# PushButton_RGB1.net
KiCad netlist of a schematic drawn in EAGLE
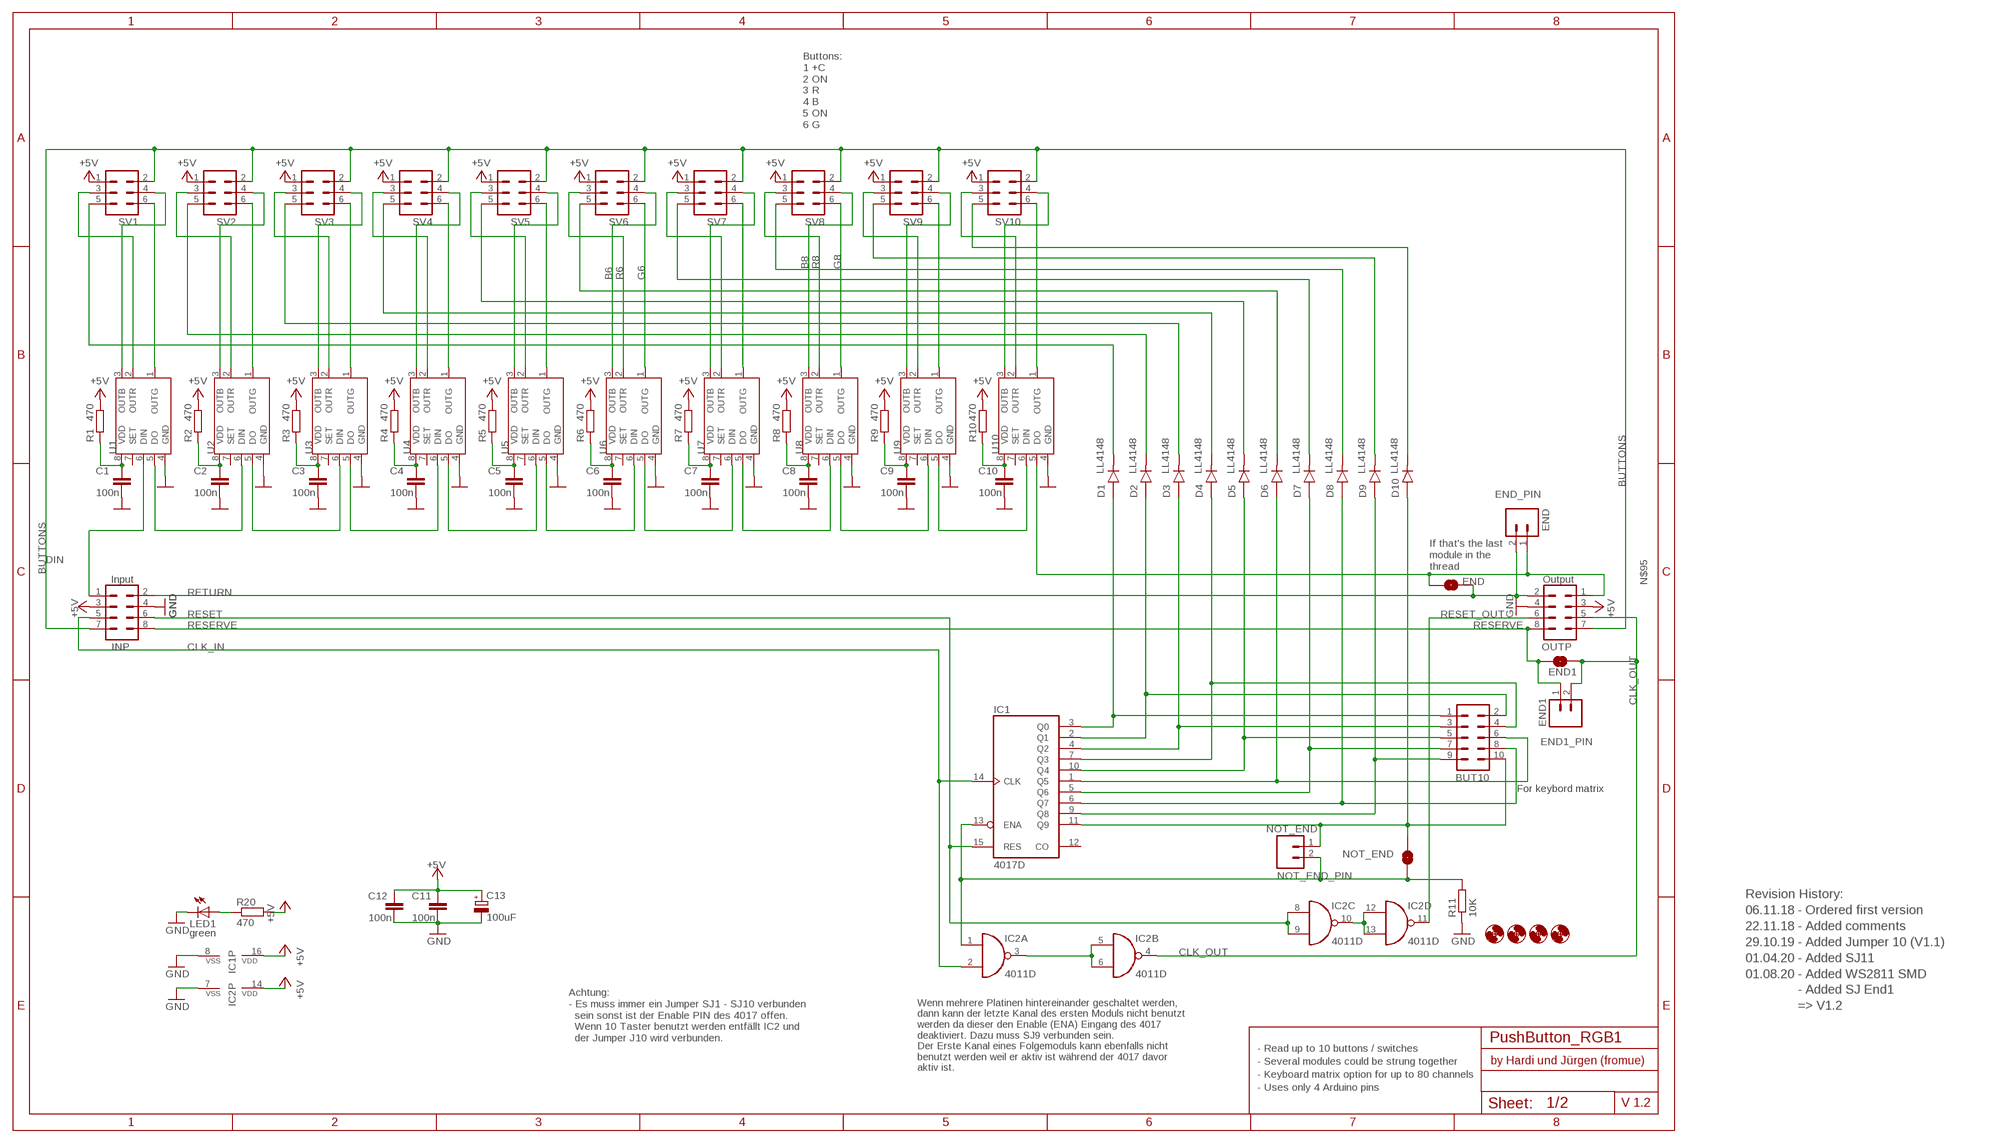
[diagram p0: schematic, sheet 1]
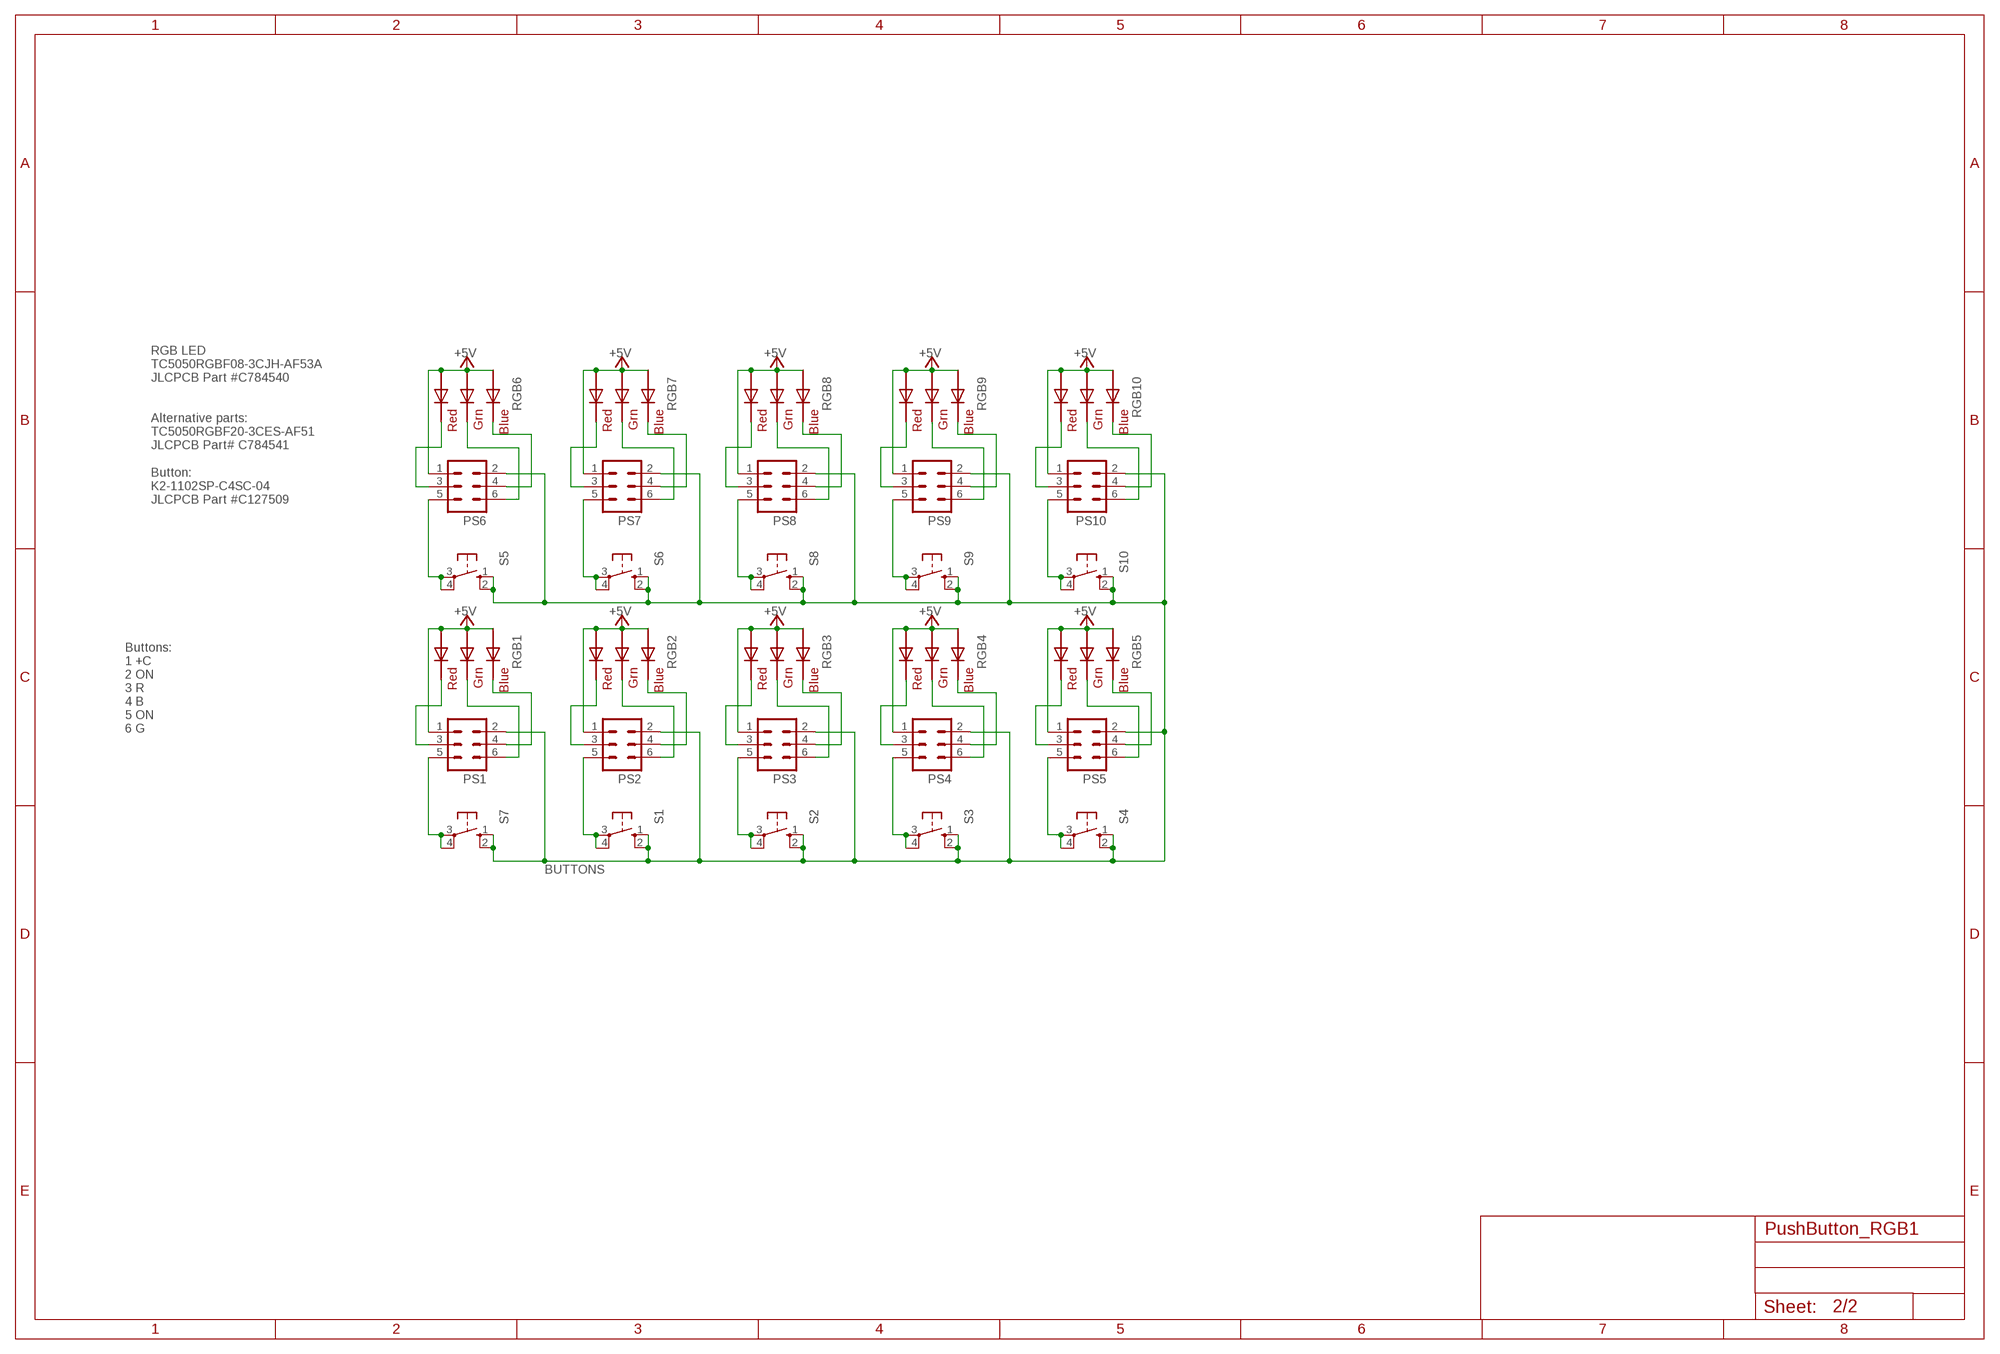
[diagram p1: schematic, sheet 2]

(export (version "E")
  (design (tool "Eeschema 10.0.6"))
  (components
    (comp (ref "PS1")
      (value "CON-HARTING-ML_ML6BKL10120958")
      (footprint "eagle-import:BKL10120958_MIRROR")
      (libsource (lib "eagle-import") (part "CON-HARTING-ML_ML6BKL10120958"))
    )
    (comp (ref "PS2")
      (value "CON-HARTING-ML_ML6BKL10120958")
      (footprint "eagle-import:BKL10120958_MIRROR")
      (libsource (lib "eagle-import") (part "CON-HARTING-ML_ML6BKL10120958"))
    )
    (comp (ref "PS3")
      (value "CON-HARTING-ML_ML6BKL10120958")
      (footprint "eagle-import:BKL10120958_MIRROR")
      (libsource (lib "eagle-import") (part "CON-HARTING-ML_ML6BKL10120958"))
    )
    (comp (ref "PS4")
      (value "CON-HARTING-ML_ML6BKL10120958")
      (footprint "eagle-import:BKL10120958_MIRROR")
      (libsource (lib "eagle-import") (part "CON-HARTING-ML_ML6BKL10120958"))
    )
    (comp (ref "PS5")
      (value "CON-HARTING-ML_ML6BKL10120958")
      (footprint "eagle-import:BKL10120958_MIRROR")
      (libsource (lib "eagle-import") (part "CON-HARTING-ML_ML6BKL10120958"))
    )
    (comp (ref "PS6")
      (value "CON-HARTING-ML_ML6BKL10120958")
      (footprint "eagle-import:BKL10120958_MIRROR")
      (libsource (lib "eagle-import") (part "CON-HARTING-ML_ML6BKL10120958"))
    )
    (comp (ref "PS7")
      (value "CON-HARTING-ML_ML6BKL10120958")
      (footprint "eagle-import:BKL10120958_MIRROR")
      (libsource (lib "eagle-import") (part "CON-HARTING-ML_ML6BKL10120958"))
    )
    (comp (ref "PS8")
      (value "CON-HARTING-ML_ML6BKL10120958")
      (footprint "eagle-import:BKL10120958_MIRROR")
      (libsource (lib "eagle-import") (part "CON-HARTING-ML_ML6BKL10120958"))
    )
    (comp (ref "PS9")
      (value "CON-HARTING-ML_ML6BKL10120958")
      (footprint "eagle-import:BKL10120958_MIRROR")
      (libsource (lib "eagle-import") (part "CON-HARTING-ML_ML6BKL10120958"))
    )
    (comp (ref "PS10")
      (value "CON-HARTING-ML_ML6BKL10120958")
      (footprint "eagle-import:BKL10120958_MIRROR")
      (libsource (lib "eagle-import") (part "CON-HARTING-ML_ML6BKL10120958"))
    )
    (comp (ref "RGB1")
      (value "RGBLED5050")
      (footprint "eagle-import:RGBLED5050")
      (libsource (lib "eagle-import") (part "RGBLED5050"))
    )
    (comp (ref "RGB2")
      (value "RGBLED5050")
      (footprint "eagle-import:RGBLED5050")
      (libsource (lib "eagle-import") (part "RGBLED5050"))
    )
    (comp (ref "RGB3")
      (value "RGBLED5050")
      (footprint "eagle-import:RGBLED5050")
      (libsource (lib "eagle-import") (part "RGBLED5050"))
    )
    (comp (ref "RGB4")
      (value "RGBLED5050")
      (footprint "eagle-import:RGBLED5050")
      (libsource (lib "eagle-import") (part "RGBLED5050"))
    )
    (comp (ref "RGB5")
      (value "RGBLED5050")
      (footprint "eagle-import:RGBLED5050")
      (libsource (lib "eagle-import") (part "RGBLED5050"))
    )
    (comp (ref "RGB6")
      (value "RGBLED5050")
      (footprint "eagle-import:RGBLED5050")
      (libsource (lib "eagle-import") (part "RGBLED5050"))
    )
    (comp (ref "RGB7")
      (value "RGBLED5050")
      (footprint "eagle-import:RGBLED5050")
      (libsource (lib "eagle-import") (part "RGBLED5050"))
    )
    (comp (ref "RGB8")
      (value "RGBLED5050")
      (footprint "eagle-import:RGBLED5050")
      (libsource (lib "eagle-import") (part "RGBLED5050"))
    )
    (comp (ref "RGB9")
      (value "RGBLED5050")
      (footprint "eagle-import:RGBLED5050")
      (libsource (lib "eagle-import") (part "RGBLED5050"))
    )
    (comp (ref "RGB10")
      (value "RGBLED5050")
      (footprint "eagle-import:RGBLED5050")
      (libsource (lib "eagle-import") (part "RGBLED5050"))
    )
    (comp (ref "S1")
      (value "10-XXB3F-10XX_SMD")
      (footprint "eagle-import:B3F-10XX_SMD")
      (libsource (lib "eagle-import") (part "10-XXB3F-10XX_SMD"))
    )
    (comp (ref "S2")
      (value "10-XXB3F-10XX_SMD")
      (footprint "eagle-import:B3F-10XX_SMD")
      (libsource (lib "eagle-import") (part "10-XXB3F-10XX_SMD"))
    )
    (comp (ref "S3")
      (value "10-XXB3F-10XX_SMD")
      (footprint "eagle-import:B3F-10XX_SMD")
      (libsource (lib "eagle-import") (part "10-XXB3F-10XX_SMD"))
    )
    (comp (ref "S4")
      (value "10-XXB3F-10XX_SMD")
      (footprint "eagle-import:B3F-10XX_SMD")
      (libsource (lib "eagle-import") (part "10-XXB3F-10XX_SMD"))
    )
    (comp (ref "S5")
      (value "10-XXB3F-10XX_SMD")
      (footprint "eagle-import:B3F-10XX_SMD")
      (libsource (lib "eagle-import") (part "10-XXB3F-10XX_SMD"))
    )
    (comp (ref "S6")
      (value "10-XXB3F-10XX_SMD")
      (footprint "eagle-import:B3F-10XX_SMD")
      (libsource (lib "eagle-import") (part "10-XXB3F-10XX_SMD"))
    )
    (comp (ref "S7")
      (value "10-XXB3F-10XX_SMD")
      (footprint "eagle-import:B3F-10XX_SMD")
      (libsource (lib "eagle-import") (part "10-XXB3F-10XX_SMD"))
    )
    (comp (ref "S8")
      (value "10-XXB3F-10XX_SMD")
      (footprint "eagle-import:B3F-10XX_SMD")
      (libsource (lib "eagle-import") (part "10-XXB3F-10XX_SMD"))
    )
    (comp (ref "S9")
      (value "10-XXB3F-10XX_SMD")
      (footprint "eagle-import:B3F-10XX_SMD")
      (libsource (lib "eagle-import") (part "10-XXB3F-10XX_SMD"))
    )
    (comp (ref "S10")
      (value "10-XXB3F-10XX_SMD")
      (footprint "eagle-import:B3F-10XX_SMD")
      (libsource (lib "eagle-import") (part "10-XXB3F-10XX_SMD"))
    )
    (comp (ref "BUT10")
      (value "CON-HARTING-ML_ML10")
      (footprint "eagle-import:CON-HARTING-ML_ML10")
      (libsource (lib "eagle-import") (part "CON-HARTING-ML_ML10"))
    )
    (comp (ref "C1")
      (value "100n")
      (footprint "eagle-import:C0603")
      (libsource (lib "eagle-import") (part "C-EUC0603"))
    )
    (comp (ref "C2")
      (value "100n")
      (footprint "eagle-import:C0603")
      (libsource (lib "eagle-import") (part "C-EUC0603"))
    )
    (comp (ref "C3")
      (value "100n")
      (footprint "eagle-import:C0603")
      (libsource (lib "eagle-import") (part "C-EUC0603"))
    )
    (comp (ref "C4")
      (value "100n")
      (footprint "eagle-import:C0603")
      (libsource (lib "eagle-import") (part "C-EUC0603"))
    )
    (comp (ref "C5")
      (value "100n")
      (footprint "eagle-import:C0603")
      (libsource (lib "eagle-import") (part "C-EUC0603"))
    )
    (comp (ref "C6")
      (value "100n")
      (footprint "eagle-import:C0603")
      (libsource (lib "eagle-import") (part "C-EUC0603"))
    )
    (comp (ref "C7")
      (value "100n")
      (footprint "eagle-import:C0603")
      (libsource (lib "eagle-import") (part "C-EUC0603"))
    )
    (comp (ref "C8")
      (value "100n")
      (footprint "eagle-import:C0603")
      (libsource (lib "eagle-import") (part "C-EUC0603"))
    )
    (comp (ref "C9")
      (value "100n")
      (footprint "eagle-import:C0603")
      (libsource (lib "eagle-import") (part "C-EUC0603"))
    )
    (comp (ref "C10")
      (value "100n")
      (footprint "eagle-import:C0603")
      (libsource (lib "eagle-import") (part "C-EUC0603"))
    )
    (comp (ref "C11")
      (value "100n")
      (footprint "eagle-import:C0603")
      (libsource (lib "eagle-import") (part "C-EUC0603"))
    )
    (comp (ref "C12")
      (value "100n")
      (footprint "eagle-import:C0603")
      (libsource (lib "eagle-import") (part "C-EUC0603"))
    )
    (comp (ref "C13")
      (value "100uF")
      (footprint "eagle-import:D_7343-31W")
      (libsource (lib "eagle-import") (part "CPOL-EUD/7343-31W"))
    )
    (comp (ref "D1")
      (value "LL4148")
      (footprint "eagle-import:DIO_LL4148")
      (fields (field (name "MF") "ON"))
      (libsource (lib "eagle-import") (part "LL4148"))
    )
    (comp (ref "D2")
      (value "LL4148")
      (footprint "eagle-import:DIO_LL4148")
      (fields (field (name "MF") "ON"))
      (libsource (lib "eagle-import") (part "LL4148"))
    )
    (comp (ref "D3")
      (value "LL4148")
      (footprint "eagle-import:DIO_LL4148")
      (fields (field (name "MF") "ON"))
      (libsource (lib "eagle-import") (part "LL4148"))
    )
    (comp (ref "D4")
      (value "LL4148")
      (footprint "eagle-import:DIO_LL4148")
      (fields (field (name "MF") "ON"))
      (libsource (lib "eagle-import") (part "LL4148"))
    )
    (comp (ref "D5")
      (value "LL4148")
      (footprint "eagle-import:DIO_LL4148")
      (fields (field (name "MF") "ON"))
      (libsource (lib "eagle-import") (part "LL4148"))
    )
    (comp (ref "D6")
      (value "LL4148")
      (footprint "eagle-import:DIO_LL4148")
      (fields (field (name "MF") "ON"))
      (libsource (lib "eagle-import") (part "LL4148"))
    )
    (comp (ref "D7")
      (value "LL4148")
      (footprint "eagle-import:DIO_LL4148")
      (fields (field (name "MF") "ON"))
      (libsource (lib "eagle-import") (part "LL4148"))
    )
    (comp (ref "D8")
      (value "LL4148")
      (footprint "eagle-import:DIO_LL4148")
      (fields (field (name "MF") "ON"))
      (libsource (lib "eagle-import") (part "LL4148"))
    )
    (comp (ref "D9")
      (value "LL4148")
      (footprint "eagle-import:DIO_LL4148")
      (fields (field (name "MF") "ON"))
      (libsource (lib "eagle-import") (part "LL4148"))
    )
    (comp (ref "D10")
      (value "LL4148")
      (footprint "eagle-import:DIO_LL4148")
      (fields (field (name "MF") "ON"))
      (libsource (lib "eagle-import") (part "LL4148"))
    )
    (comp (ref "END")
      (value "SOLDERJUMPERNO")
      (footprint "eagle-import:SJ_2S-NO")
      (libsource (lib "eagle-import") (part "SOLDERJUMPERNO"))
    )
    (comp (ref "END1")
      (value "SOLDERJUMPERNO")
      (footprint "eagle-import:SJ_2S-NO")
      (libsource (lib "eagle-import") (part "SOLDERJUMPERNO"))
    )
    (comp (ref "END1_PIN")
      (value "END1")
      (footprint "eagle-import:1X02")
      (libsource (lib "eagle-import") (part "M02PTH"))
    )
    (comp (ref "END_PIN")
      (value "END")
      (footprint "eagle-import:1X02")
      (libsource (lib "eagle-import") (part "M02PTH"))
    )
    (comp (ref "H1")
      (value "MOUNT-HOLE3.0")
      (footprint "eagle-import:3,0")
      (libsource (lib "eagle-import") (part "MOUNT-HOLE3.0"))
    )
    (comp (ref "H2")
      (value "MOUNT-HOLE3.0")
      (footprint "eagle-import:3,0")
      (libsource (lib "eagle-import") (part "MOUNT-HOLE3.0"))
    )
    (comp (ref "H3")
      (value "MOUNT-HOLE3.0")
      (footprint "eagle-import:3,0")
      (libsource (lib "eagle-import") (part "MOUNT-HOLE3.0"))
    )
    (comp (ref "H4")
      (value "MOUNT-HOLE2.8")
      (footprint "eagle-import:2,8")
      (libsource (lib "eagle-import") (part "MOUNT-HOLE2.8"))
    )
    (comp (ref "IC1")
      (value "4017D")
      (footprint "eagle-import:SO16")
      (libsource (lib "eagle-import") (part "4017D"))
    )
    (comp (ref "IC2")
      (value "4011D")
      (footprint "eagle-import:SO14")
      (fields (field (name "SPICEPREFIX") "J"))
      (libsource (lib "eagle-import") (part "4011D"))
    )
    (comp (ref "INP")
      (value "CON-HARTING-ML_ML08")
      (footprint "eagle-import:CON-HARTING-ML_ML08")
      (libsource (lib "eagle-import") (part "CON-HARTING-ML_ML08"))
    )
    (comp (ref "LED1")
      (value "green")
      (footprint "eagle-import:LED3MM")
      (libsource (lib "eagle-import") (part "LED3MM"))
    )
    (comp (ref "NOT_END")
      (value "SOLDERJUMPERNO")
      (footprint "eagle-import:SJ_2S-NO")
      (libsource (lib "eagle-import") (part "SOLDERJUMPERNO"))
    )
    (comp (ref "NOT_END_PIN")
      (value "NOT_END")
      (footprint "eagle-import:1X02")
      (libsource (lib "eagle-import") (part "M02PTH"))
    )
    (comp (ref "OUTP")
      (value "CON-HARTING-ML_ML08")
      (footprint "eagle-import:CON-HARTING-ML_ML08")
      (libsource (lib "eagle-import") (part "CON-HARTING-ML_ML08"))
    )
    (comp (ref "R1")
      (value "470")
      (footprint "eagle-import:R0603")
      (libsource (lib "eagle-import") (part "R-EU_R0603"))
    )
    (comp (ref "R2")
      (value "470")
      (footprint "eagle-import:R0603")
      (libsource (lib "eagle-import") (part "R-EU_R0603"))
    )
    (comp (ref "R3")
      (value "470")
      (footprint "eagle-import:R0603")
      (libsource (lib "eagle-import") (part "R-EU_R0603"))
    )
    (comp (ref "R4")
      (value "470")
      (footprint "eagle-import:R0603")
      (libsource (lib "eagle-import") (part "R-EU_R0603"))
    )
    (comp (ref "R5")
      (value "470")
      (footprint "eagle-import:R0603")
      (libsource (lib "eagle-import") (part "R-EU_R0603"))
    )
    (comp (ref "R6")
      (value "470")
      (footprint "eagle-import:R0603")
      (libsource (lib "eagle-import") (part "R-EU_R0603"))
    )
    (comp (ref "R7")
      (value "470")
      (footprint "eagle-import:R0603")
      (libsource (lib "eagle-import") (part "R-EU_R0603"))
    )
    (comp (ref "R8")
      (value "470")
      (footprint "eagle-import:R0603")
      (libsource (lib "eagle-import") (part "R-EU_R0603"))
    )
    (comp (ref "R9")
      (value "470")
      (footprint "eagle-import:R0603")
      (libsource (lib "eagle-import") (part "R-EU_R0603"))
    )
    (comp (ref "R10")
      (value "470")
      (footprint "eagle-import:R0603")
      (libsource (lib "eagle-import") (part "R-EU_R0603"))
    )
    (comp (ref "R11")
      (value "10K")
      (footprint "eagle-import:R0603")
      (libsource (lib "eagle-import") (part "R-EU_R0603"))
    )
    (comp (ref "R20")
      (value "470")
      (footprint "eagle-import:R0603")
      (libsource (lib "eagle-import") (part "R-EU_R0603"))
    )
    (comp (ref "SV1")
      (value "CON-HARTING-ML_ML6")
      (footprint "eagle-import:CON-HARTING-ML_ML6")
      (libsource (lib "eagle-import") (part "CON-HARTING-ML_ML6"))
    )
    (comp (ref "SV2")
      (value "CON-HARTING-ML_ML6")
      (footprint "eagle-import:CON-HARTING-ML_ML6")
      (libsource (lib "eagle-import") (part "CON-HARTING-ML_ML6"))
    )
    (comp (ref "SV3")
      (value "CON-HARTING-ML_ML6")
      (footprint "eagle-import:CON-HARTING-ML_ML6")
      (libsource (lib "eagle-import") (part "CON-HARTING-ML_ML6"))
    )
    (comp (ref "SV4")
      (value "CON-HARTING-ML_ML6")
      (footprint "eagle-import:CON-HARTING-ML_ML6")
      (libsource (lib "eagle-import") (part "CON-HARTING-ML_ML6"))
    )
    (comp (ref "SV5")
      (value "CON-HARTING-ML_ML6")
      (footprint "eagle-import:CON-HARTING-ML_ML6")
      (libsource (lib "eagle-import") (part "CON-HARTING-ML_ML6"))
    )
    (comp (ref "SV6")
      (value "CON-HARTING-ML_ML6")
      (footprint "eagle-import:CON-HARTING-ML_ML6")
      (libsource (lib "eagle-import") (part "CON-HARTING-ML_ML6"))
    )
    (comp (ref "SV7")
      (value "CON-HARTING-ML_ML6")
      (footprint "eagle-import:CON-HARTING-ML_ML6")
      (libsource (lib "eagle-import") (part "CON-HARTING-ML_ML6"))
    )
    (comp (ref "SV8")
      (value "CON-HARTING-ML_ML6")
      (footprint "eagle-import:CON-HARTING-ML_ML6")
      (libsource (lib "eagle-import") (part "CON-HARTING-ML_ML6"))
    )
    (comp (ref "SV9")
      (value "CON-HARTING-ML_ML6")
      (footprint "eagle-import:CON-HARTING-ML_ML6")
      (libsource (lib "eagle-import") (part "CON-HARTING-ML_ML6"))
    )
    (comp (ref "SV10")
      (value "CON-HARTING-ML_ML6")
      (footprint "eagle-import:CON-HARTING-ML_ML6")
      (libsource (lib "eagle-import") (part "CON-HARTING-ML_ML6"))
    )
    (comp (ref "U1")
      (value "S3PO_MODUL_WS2811_SOUND_MP3-TF-16P_WS2811_AND_ATTINY_WS2811-ICSOP8")
      (footprint "eagle-import:SOP8")
      (libsource (lib "eagle-import") (part "S3PO_MODUL_WS2811_SOUND_MP3-TF-16P_WS2811_AND_ATTINY_WS2811-ICSOP8"))
    )
    (comp (ref "U2")
      (value "S3PO_MODUL_WS2811_SOUND_MP3-TF-16P_WS2811_AND_ATTINY_WS2811-ICSOP8")
      (footprint "eagle-import:SOP8")
      (libsource (lib "eagle-import") (part "S3PO_MODUL_WS2811_SOUND_MP3-TF-16P_WS2811_AND_ATTINY_WS2811-ICSOP8"))
    )
    (comp (ref "U3")
      (value "S3PO_MODUL_WS2811_SOUND_MP3-TF-16P_WS2811_AND_ATTINY_WS2811-ICSOP8")
      (footprint "eagle-import:SOP8")
      (libsource (lib "eagle-import") (part "S3PO_MODUL_WS2811_SOUND_MP3-TF-16P_WS2811_AND_ATTINY_WS2811-ICSOP8"))
    )
    (comp (ref "U4")
      (value "S3PO_MODUL_WS2811_SOUND_MP3-TF-16P_WS2811_AND_ATTINY_WS2811-ICSOP8")
      (footprint "eagle-import:SOP8")
      (libsource (lib "eagle-import") (part "S3PO_MODUL_WS2811_SOUND_MP3-TF-16P_WS2811_AND_ATTINY_WS2811-ICSOP8"))
    )
    (comp (ref "U5")
      (value "S3PO_MODUL_WS2811_SOUND_MP3-TF-16P_WS2811_AND_ATTINY_WS2811-ICSOP8")
      (footprint "eagle-import:SOP8")
      (libsource (lib "eagle-import") (part "S3PO_MODUL_WS2811_SOUND_MP3-TF-16P_WS2811_AND_ATTINY_WS2811-ICSOP8"))
    )
    (comp (ref "U6")
      (value "S3PO_MODUL_WS2811_SOUND_MP3-TF-16P_WS2811_AND_ATTINY_WS2811-ICSOP8")
      (footprint "eagle-import:SOP8")
      (libsource (lib "eagle-import") (part "S3PO_MODUL_WS2811_SOUND_MP3-TF-16P_WS2811_AND_ATTINY_WS2811-ICSOP8"))
    )
    (comp (ref "U7")
      (value "S3PO_MODUL_WS2811_SOUND_MP3-TF-16P_WS2811_AND_ATTINY_WS2811-ICSOP8")
      (footprint "eagle-import:SOP8")
      (libsource (lib "eagle-import") (part "S3PO_MODUL_WS2811_SOUND_MP3-TF-16P_WS2811_AND_ATTINY_WS2811-ICSOP8"))
    )
    (comp (ref "U8")
      (value "S3PO_MODUL_WS2811_SOUND_MP3-TF-16P_WS2811_AND_ATTINY_WS2811-ICSOP8")
      (footprint "eagle-import:SOP8")
      (libsource (lib "eagle-import") (part "S3PO_MODUL_WS2811_SOUND_MP3-TF-16P_WS2811_AND_ATTINY_WS2811-ICSOP8"))
    )
    (comp (ref "U9")
      (value "S3PO_MODUL_WS2811_SOUND_MP3-TF-16P_WS2811_AND_ATTINY_WS2811-ICSOP8")
      (footprint "eagle-import:SOP8")
      (libsource (lib "eagle-import") (part "S3PO_MODUL_WS2811_SOUND_MP3-TF-16P_WS2811_AND_ATTINY_WS2811-ICSOP8"))
    )
    (comp (ref "U10")
      (value "S3PO_MODUL_WS2811_SOUND_MP3-TF-16P_WS2811_AND_ATTINY_WS2811-ICSOP8")
      (footprint "eagle-import:SOP8")
      (libsource (lib "eagle-import") (part "S3PO_MODUL_WS2811_SOUND_MP3-TF-16P_WS2811_AND_ATTINY_WS2811-ICSOP8"))
    )
  )
  (nets
    (net (code "1") (name "+5V") (class "Default")
      (node (ref "C11") (pin "1") (pinfunction "1_1") (pintype "passive"))
      (node (ref "C12") (pin "1") (pinfunction "1_1") (pintype "passive"))
      (node (ref "C13") (pin "+") (pinfunction "+_+") (pintype "passive"))
      (node (ref "IC1") (pin "16") (pinfunction "VDD_16") (pintype "power_in"))
      (node (ref "IC2") (pin "14") (pinfunction "VDD_14") (pintype "power_in"))
      (node (ref "INP") (pin "3") (pinfunction "3_3") (pintype "passive"))
      (node (ref "OUTP") (pin "3") (pinfunction "3_3") (pintype "passive"))
      (node (ref "PS1") (pin "1") (pinfunction "1_1") (pintype "passive"))
      (node (ref "PS10") (pin "1") (pinfunction "1_1") (pintype "passive"))
      (node (ref "PS2") (pin "1") (pinfunction "1_1") (pintype "passive"))
      (node (ref "PS3") (pin "1") (pinfunction "1_1") (pintype "passive"))
      (node (ref "PS4") (pin "1") (pinfunction "1_1") (pintype "passive"))
      (node (ref "PS5") (pin "1") (pinfunction "1_1") (pintype "passive"))
      (node (ref "PS6") (pin "1") (pinfunction "1_1") (pintype "passive"))
      (node (ref "PS7") (pin "1") (pinfunction "1_1") (pintype "passive"))
      (node (ref "PS8") (pin "1") (pinfunction "1_1") (pintype "passive"))
      (node (ref "PS9") (pin "1") (pinfunction "1_1") (pintype "passive"))
      (node (ref "R1") (pin "2") (pinfunction "2_2") (pintype "passive"))
      (node (ref "R10") (pin "2") (pinfunction "2_2") (pintype "passive"))
      (node (ref "R2") (pin "2") (pinfunction "2_2") (pintype "passive"))
      (node (ref "R20") (pin "2") (pinfunction "2_2") (pintype "passive"))
      (node (ref "R3") (pin "2") (pinfunction "2_2") (pintype "passive"))
      (node (ref "R4") (pin "2") (pinfunction "2_2") (pintype "passive"))
      (node (ref "R5") (pin "2") (pinfunction "2_2") (pintype "passive"))
      (node (ref "R6") (pin "2") (pinfunction "2_2") (pintype "passive"))
      (node (ref "R7") (pin "2") (pinfunction "2_2") (pintype "passive"))
      (node (ref "R8") (pin "2") (pinfunction "2_2") (pintype "passive"))
      (node (ref "R9") (pin "2") (pinfunction "2_2") (pintype "passive"))
      (node (ref "RGB1") (pin "1") (pinfunction "GREEN_A_1") (pintype "bidirectional"))
      (node (ref "RGB1") (pin "2") (pinfunction "RED_A_2") (pintype "bidirectional"))
      (node (ref "RGB1") (pin "3") (pinfunction "BLUE_A_3") (pintype "bidirectional"))
      (node (ref "RGB10") (pin "1") (pinfunction "GREEN_A_1") (pintype "bidirectional"))
      (node (ref "RGB10") (pin "2") (pinfunction "RED_A_2") (pintype "bidirectional"))
      (node (ref "RGB10") (pin "3") (pinfunction "BLUE_A_3") (pintype "bidirectional"))
      (node (ref "RGB2") (pin "1") (pinfunction "GREEN_A_1") (pintype "bidirectional"))
      (node (ref "RGB2") (pin "2") (pinfunction "RED_A_2") (pintype "bidirectional"))
      (node (ref "RGB2") (pin "3") (pinfunction "BLUE_A_3") (pintype "bidirectional"))
      (node (ref "RGB3") (pin "1") (pinfunction "GREEN_A_1") (pintype "bidirectional"))
      (node (ref "RGB3") (pin "2") (pinfunction "RED_A_2") (pintype "bidirectional"))
      (node (ref "RGB3") (pin "3") (pinfunction "BLUE_A_3") (pintype "bidirectional"))
      (node (ref "RGB4") (pin "1") (pinfunction "GREEN_A_1") (pintype "bidirectional"))
      (node (ref "RGB4") (pin "2") (pinfunction "RED_A_2") (pintype "bidirectional"))
      (node (ref "RGB4") (pin "3") (pinfunction "BLUE_A_3") (pintype "bidirectional"))
      (node (ref "RGB5") (pin "1") (pinfunction "GREEN_A_1") (pintype "bidirectional"))
      (node (ref "RGB5") (pin "2") (pinfunction "RED_A_2") (pintype "bidirectional"))
      (node (ref "RGB5") (pin "3") (pinfunction "BLUE_A_3") (pintype "bidirectional"))
      (node (ref "RGB6") (pin "1") (pinfunction "GREEN_A_1") (pintype "bidirectional"))
      (node (ref "RGB6") (pin "2") (pinfunction "RED_A_2") (pintype "bidirectional"))
      (node (ref "RGB6") (pin "3") (pinfunction "BLUE_A_3") (pintype "bidirectional"))
      (node (ref "RGB7") (pin "1") (pinfunction "GREEN_A_1") (pintype "bidirectional"))
      (node (ref "RGB7") (pin "2") (pinfunction "RED_A_2") (pintype "bidirectional"))
      (node (ref "RGB7") (pin "3") (pinfunction "BLUE_A_3") (pintype "bidirectional"))
      (node (ref "RGB8") (pin "1") (pinfunction "GREEN_A_1") (pintype "bidirectional"))
      (node (ref "RGB8") (pin "2") (pinfunction "RED_A_2") (pintype "bidirectional"))
      (node (ref "RGB8") (pin "3") (pinfunction "BLUE_A_3") (pintype "bidirectional"))
      (node (ref "RGB9") (pin "1") (pinfunction "GREEN_A_1") (pintype "bidirectional"))
      (node (ref "RGB9") (pin "2") (pinfunction "RED_A_2") (pintype "bidirectional"))
      (node (ref "RGB9") (pin "3") (pinfunction "BLUE_A_3") (pintype "bidirectional"))
      (node (ref "SV1") (pin "1") (pinfunction "1_1") (pintype "passive"))
      (node (ref "SV10") (pin "1") (pinfunction "1_1") (pintype "passive"))
      (node (ref "SV2") (pin "1") (pinfunction "1_1") (pintype "passive"))
      (node (ref "SV3") (pin "1") (pinfunction "1_1") (pintype "passive"))
      (node (ref "SV4") (pin "1") (pinfunction "1_1") (pintype "passive"))
      (node (ref "SV5") (pin "1") (pinfunction "1_1") (pintype "passive"))
      (node (ref "SV6") (pin "1") (pinfunction "1_1") (pintype "passive"))
      (node (ref "SV7") (pin "1") (pinfunction "1_1") (pintype "passive"))
      (node (ref "SV8") (pin "1") (pinfunction "1_1") (pintype "passive"))
      (node (ref "SV9") (pin "1") (pinfunction "1_1") (pintype "passive"))
    )
    (net (code "2") (name "B6") (class "Default")
      (node (ref "SV6") (pin "4") (pinfunction "4_4") (pintype "passive"))
      (node (ref "U6") (pin "3") (pinfunction "OUTB_3") (pintype "open_collector"))
    )
    (net (code "3") (name "B8") (class "Default")
      (node (ref "SV8") (pin "4") (pinfunction "4_4") (pintype "passive"))
      (node (ref "U8") (pin "3") (pinfunction "OUTB_3") (pintype "open_collector"))
    )
    (net (code "4") (name "BUTTONS") (class "Default")
      (node (ref "INP") (pin "7") (pinfunction "7_7") (pintype "passive"))
      (node (ref "OUTP") (pin "7") (pinfunction "7_7") (pintype "passive"))
      (node (ref "PS1") (pin "2") (pinfunction "2_2") (pintype "passive"))
      (node (ref "PS10") (pin "2") (pinfunction "2_2") (pintype "passive"))
      (node (ref "PS2") (pin "2") (pinfunction "2_2") (pintype "passive"))
      (node (ref "PS3") (pin "2") (pinfunction "2_2") (pintype "passive"))
      (node (ref "PS4") (pin "2") (pinfunction "2_2") (pintype "passive"))
      (node (ref "PS5") (pin "2") (pinfunction "2_2") (pintype "passive"))
      (node (ref "PS6") (pin "2") (pinfunction "2_2") (pintype "passive"))
      (node (ref "PS7") (pin "2") (pinfunction "2_2") (pintype "passive"))
      (node (ref "PS8") (pin "2") (pinfunction "2_2") (pintype "passive"))
      (node (ref "PS9") (pin "2") (pinfunction "2_2") (pintype "passive"))
      (node (ref "S1") (pin "1") (pinfunction "S_1") (pintype "passive"))
      (node (ref "S1") (pin "2") (pinfunction "S1_2") (pintype "passive"))
      (node (ref "S10") (pin "1") (pinfunction "S_1") (pintype "passive"))
      (node (ref "S10") (pin "2") (pinfunction "S1_2") (pintype "passive"))
      (node (ref "S2") (pin "1") (pinfunction "S_1") (pintype "passive"))
      (node (ref "S2") (pin "2") (pinfunction "S1_2") (pintype "passive"))
      (node (ref "S3") (pin "1") (pinfunction "S_1") (pintype "passive"))
      (node (ref "S3") (pin "2") (pinfunction "S1_2") (pintype "passive"))
      (node (ref "S4") (pin "1") (pinfunction "S_1") (pintype "passive"))
      (node (ref "S4") (pin "2") (pinfunction "S1_2") (pintype "passive"))
      (node (ref "S5") (pin "1") (pinfunction "S_1") (pintype "passive"))
      (node (ref "S5") (pin "2") (pinfunction "S1_2") (pintype "passive"))
      (node (ref "S6") (pin "1") (pinfunction "S_1") (pintype "passive"))
      (node (ref "S6") (pin "2") (pinfunction "S1_2") (pintype "passive"))
      (node (ref "S7") (pin "1") (pinfunction "S_1") (pintype "passive"))
      (node (ref "S7") (pin "2") (pinfunction "S1_2") (pintype "passive"))
      (node (ref "S8") (pin "1") (pinfunction "S_1") (pintype "passive"))
      (node (ref "S8") (pin "2") (pinfunction "S1_2") (pintype "passive"))
      (node (ref "S9") (pin "1") (pinfunction "S_1") (pintype "passive"))
      (node (ref "S9") (pin "2") (pinfunction "S1_2") (pintype "passive"))
      (node (ref "SV1") (pin "2") (pinfunction "2_2") (pintype "passive"))
      (node (ref "SV10") (pin "2") (pinfunction "2_2") (pintype "passive"))
      (node (ref "SV2") (pin "2") (pinfunction "2_2") (pintype "passive"))
      (node (ref "SV3") (pin "2") (pinfunction "2_2") (pintype "passive"))
      (node (ref "SV4") (pin "2") (pinfunction "2_2") (pintype "passive"))
      (node (ref "SV5") (pin "2") (pinfunction "2_2") (pintype "passive"))
      (node (ref "SV6") (pin "2") (pinfunction "2_2") (pintype "passive"))
      (node (ref "SV7") (pin "2") (pinfunction "2_2") (pintype "passive"))
      (node (ref "SV8") (pin "2") (pinfunction "2_2") (pintype "passive"))
      (node (ref "SV9") (pin "2") (pinfunction "2_2") (pintype "passive"))
    )
    (net (code "5") (name "CLK_IN") (class "Default")
      (node (ref "IC1") (pin "14") (pinfunction "CLK_14") (pintype "input"))
      (node (ref "IC2") (pin "2") (pinfunction "I1_2") (pintype "input"))
      (node (ref "INP") (pin "5") (pinfunction "5_5") (pintype "passive"))
    )
    (net (code "6") (name "CLK_OUT") (class "Default")
      (node (ref "END1") (pin "1") (pinfunction "1_1") (pintype "passive"))
      (node (ref "END1_PIN") (pin "2") (pinfunction "2_2") (pintype "passive"))
      (node (ref "IC2") (pin "4") (pinfunction "O_4") (pintype "output"))
      (node (ref "OUTP") (pin "5") (pinfunction "5_5") (pintype "passive"))
    )
    (net (code "7") (name "DIN") (class "Default")
      (node (ref "INP") (pin "1") (pinfunction "1_1") (pintype "passive"))
      (node (ref "U1") (pin "6") (pinfunction "DIN_6") (pintype "input"))
    )
    (net (code "8") (name "G6") (class "Default")
      (node (ref "SV6") (pin "6") (pinfunction "6_6") (pintype "passive"))
      (node (ref "U6") (pin "1") (pinfunction "OUTG_1") (pintype "open_collector"))
    )
    (net (code "9") (name "G8") (class "Default")
      (node (ref "SV8") (pin "6") (pinfunction "6_6") (pintype "passive"))
      (node (ref "U8") (pin "1") (pinfunction "OUTG_1") (pintype "open_collector"))
    )
    (net (code "10") (name "GND") (class "Default")
      (node (ref "C1") (pin "2") (pinfunction "2_2") (pintype "passive"))
      (node (ref "C10") (pin "2") (pinfunction "2_2") (pintype "passive"))
      (node (ref "C11") (pin "2") (pinfunction "2_2") (pintype "passive"))
      (node (ref "C12") (pin "2") (pinfunction "2_2") (pintype "passive"))
      (node (ref "C13") (pin "-") (pinfunction "-_-") (pintype "passive"))
      (node (ref "C2") (pin "2") (pinfunction "2_2") (pintype "passive"))
      (node (ref "C3") (pin "2") (pinfunction "2_2") (pintype "passive"))
      (node (ref "C4") (pin "2") (pinfunction "2_2") (pintype "passive"))
      (node (ref "C5") (pin "2") (pinfunction "2_2") (pintype "passive"))
      (node (ref "C6") (pin "2") (pinfunction "2_2") (pintype "passive"))
      (node (ref "C7") (pin "2") (pinfunction "2_2") (pintype "passive"))
      (node (ref "C8") (pin "2") (pinfunction "2_2") (pintype "passive"))
      (node (ref "C9") (pin "2") (pinfunction "2_2") (pintype "passive"))
      (node (ref "IC1") (pin "8") (pinfunction "VSS_8") (pintype "power_in"))
      (node (ref "IC2") (pin "7") (pinfunction "VSS_7") (pintype "power_in"))
      (node (ref "INP") (pin "4") (pinfunction "4_4") (pintype "passive"))
      (node (ref "LED1") (pin "K") (pinfunction "C_K") (pintype "passive"))
      (node (ref "OUTP") (pin "4") (pinfunction "4_4") (pintype "passive"))
      (node (ref "R11") (pin "1") (pinfunction "1_1") (pintype "passive"))
      (node (ref "U1") (pin "4") (pinfunction "GND_4") (pintype "power_in"))
      (node (ref "U10") (pin "4") (pinfunction "GND_4") (pintype "power_in"))
      (node (ref "U2") (pin "4") (pinfunction "GND_4") (pintype "power_in"))
      (node (ref "U3") (pin "4") (pinfunction "GND_4") (pintype "power_in"))
      (node (ref "U4") (pin "4") (pinfunction "GND_4") (pintype "power_in"))
      (node (ref "U5") (pin "4") (pinfunction "GND_4") (pintype "power_in"))
      (node (ref "U6") (pin "4") (pinfunction "GND_4") (pintype "power_in"))
      (node (ref "U7") (pin "4") (pinfunction "GND_4") (pintype "power_in"))
      (node (ref "U8") (pin "4") (pinfunction "GND_4") (pintype "power_in"))
      (node (ref "U9") (pin "4") (pinfunction "GND_4") (pintype "power_in"))
    )
    (net (code "11") (name "N$95") (class "Default")
      (node (ref "END") (pin "2") (pinfunction "2_2") (pintype "passive"))
      (node (ref "END_PIN") (pin "1") (pinfunction "1_1") (pintype "passive"))
      (node (ref "OUTP") (pin "1") (pinfunction "1_1") (pintype "passive"))
      (node (ref "U10") (pin "5") (pinfunction "DO_5") (pintype "output"))
    )
    (net (code "12") (name "Net-(D1-PadC)") (class "Default")
      (node (ref "D1") (pin "C") (pinfunction "C_C") (pintype "passive"))
      (node (ref "SV1") (pin "5") (pinfunction "5_5") (pintype "passive"))
    )
    (net (code "13") (name "Net-(D2-PadC)") (class "Default")
      (node (ref "D2") (pin "C") (pinfunction "C_C") (pintype "passive"))
      (node (ref "SV2") (pin "5") (pinfunction "5_5") (pintype "passive"))
    )
    (net (code "14") (name "Net-(D3-PadC)") (class "Default")
      (node (ref "D3") (pin "C") (pinfunction "C_C") (pintype "passive"))
      (node (ref "SV3") (pin "5") (pinfunction "5_5") (pintype "passive"))
    )
    (net (code "15") (name "Net-(D4-PadC)") (class "Default")
      (node (ref "D4") (pin "C") (pinfunction "C_C") (pintype "passive"))
      (node (ref "SV4") (pin "5") (pinfunction "5_5") (pintype "passive"))
    )
    (net (code "16") (name "Net-(D5-PadC)") (class "Default")
      (node (ref "D5") (pin "C") (pinfunction "C_C") (pintype "passive"))
      (node (ref "SV5") (pin "5") (pinfunction "5_5") (pintype "passive"))
    )
    (net (code "17") (name "Net-(D6-PadC)") (class "Default")
      (node (ref "D6") (pin "C") (pinfunction "C_C") (pintype "passive"))
      (node (ref "SV6") (pin "5") (pinfunction "5_5") (pintype "passive"))
    )
    (net (code "18") (name "Net-(D7-PadC)") (class "Default")
      (node (ref "D7") (pin "C") (pinfunction "C_C") (pintype "passive"))
      (node (ref "SV7") (pin "5") (pinfunction "5_5") (pintype "passive"))
    )
    (net (code "19") (name "Net-(D8-PadC)") (class "Default")
      (node (ref "D8") (pin "C") (pinfunction "C_C") (pintype "passive"))
      (node (ref "SV8") (pin "5") (pinfunction "5_5") (pintype "passive"))
    )
    (net (code "20") (name "Net-(D9-PadC)") (class "Default")
      (node (ref "D9") (pin "C") (pinfunction "C_C") (pintype "passive"))
      (node (ref "SV9") (pin "5") (pinfunction "5_5") (pintype "passive"))
    )
    (net (code "21") (name "Net-(D10-PadC)") (class "Default")
      (node (ref "D10") (pin "C") (pinfunction "C_C") (pintype "passive"))
      (node (ref "SV10") (pin "5") (pinfunction "5_5") (pintype "passive"))
    )
    (net (code "22") (name "Net-(IC1A-ENA)") (class "Default")
      (node (ref "IC1") (pin "13") (pinfunction "ENA_13") (pintype "input"))
      (node (ref "IC2") (pin "1") (pinfunction "I0_1") (pintype "input"))
      (node (ref "NOT_END") (pin "1") (pinfunction "1_1") (pintype "passive"))
      (node (ref "NOT_END_PIN") (pin "2") (pinfunction "2_2") (pintype "passive"))
      (node (ref "R11") (pin "2") (pinfunction "2_2") (pintype "passive"))
    )
    (net (code "23") (name "Net-(IC1A-Q0)") (class "Default")
      (node (ref "BUT10") (pin "1") (pinfunction "1_1") (pintype "passive"))
      (node (ref "D1") (pin "A") (pinfunction "A_A") (pintype "passive"))
      (node (ref "IC1") (pin "3") (pinfunction "Q0_3") (pintype "output"))
    )
    (net (code "24") (name "Net-(IC1A-Q1)") (class "Default")
      (node (ref "BUT10") (pin "2") (pinfunction "2_2") (pintype "passive"))
      (node (ref "D2") (pin "A") (pinfunction "A_A") (pintype "passive"))
      (node (ref "IC1") (pin "2") (pinfunction "Q1_2") (pintype "output"))
    )
    (net (code "25") (name "Net-(IC1A-Q2)") (class "Default")
      (node (ref "BUT10") (pin "3") (pinfunction "3_3") (pintype "passive"))
      (node (ref "D3") (pin "A") (pinfunction "A_A") (pintype "passive"))
      (node (ref "IC1") (pin "4") (pinfunction "Q2_4") (pintype "output"))
    )
    (net (code "26") (name "Net-(IC1A-Q3)") (class "Default")
      (node (ref "BUT10") (pin "4") (pinfunction "4_4") (pintype "passive"))
      (node (ref "D4") (pin "A") (pinfunction "A_A") (pintype "passive"))
      (node (ref "IC1") (pin "7") (pinfunction "Q3_7") (pintype "output"))
    )
    (net (code "27") (name "Net-(IC1A-Q4)") (class "Default")
      (node (ref "BUT10") (pin "5") (pinfunction "5_5") (pintype "passive"))
      (node (ref "D5") (pin "A") (pinfunction "A_A") (pintype "passive"))
      (node (ref "IC1") (pin "10") (pinfunction "Q4_10") (pintype "output"))
    )
    (net (code "28") (name "Net-(IC1A-Q5)") (class "Default")
      (node (ref "BUT10") (pin "6") (pinfunction "6_6") (pintype "passive"))
      (node (ref "D6") (pin "A") (pinfunction "A_A") (pintype "passive"))
      (node (ref "IC1") (pin "1") (pinfunction "Q5_1") (pintype "output"))
    )
    (net (code "29") (name "Net-(IC1A-Q6)") (class "Default")
      (node (ref "BUT10") (pin "7") (pinfunction "7_7") (pintype "passive"))
      (node (ref "D7") (pin "A") (pinfunction "A_A") (pintype "passive"))
      (node (ref "IC1") (pin "5") (pinfunction "Q6_5") (pintype "output"))
    )
    (net (code "30") (name "Net-(IC1A-Q7)") (class "Default")
      (node (ref "BUT10") (pin "8") (pinfunction "8_8") (pintype "passive"))
      (node (ref "D8") (pin "A") (pinfunction "A_A") (pintype "passive"))
      (node (ref "IC1") (pin "6") (pinfunction "Q7_6") (pintype "output"))
    )
    (net (code "31") (name "Net-(IC1A-Q8)") (class "Default")
      (node (ref "BUT10") (pin "9") (pinfunction "9_9") (pintype "passive"))
      (node (ref "D9") (pin "A") (pinfunction "A_A") (pintype "passive"))
      (node (ref "IC1") (pin "9") (pinfunction "Q8_9") (pintype "output"))
    )
    (net (code "32") (name "Net-(IC1A-Q9)") (class "Default")
      (node (ref "BUT10") (pin "10") (pinfunction "10_10") (pintype "passive"))
      (node (ref "D10") (pin "A") (pinfunction "A_A") (pintype "passive"))
      (node (ref "IC1") (pin "11") (pinfunction "Q9_11") (pintype "output"))
      (node (ref "NOT_END") (pin "2") (pinfunction "2_2") (pintype "passive"))
      (node (ref "NOT_END_PIN") (pin "1") (pinfunction "1_1") (pintype "passive"))
    )
    (net (code "33") (name "Net-(IC2A-O)") (class "Default")
      (node (ref "IC2") (pin "3") (pinfunction "O_3") (pintype "output"))
      (node (ref "IC2") (pin "5") (pinfunction "I0_5") (pintype "input"))
      (node (ref "IC2") (pin "6") (pinfunction "I1_6") (pintype "input"))
    )
    (net (code "34") (name "Net-(IC2C-O)") (class "Default")
      (node (ref "IC2") (pin "10") (pinfunction "O_10") (pintype "output"))
      (node (ref "IC2") (pin "12") (pinfunction "I0_12") (pintype "input"))
      (node (ref "IC2") (pin "13") (pinfunction "I1_13") (pintype "input"))
    )
    (net (code "35") (name "Net-(LED1-PadA)") (class "Default")
      (node (ref "LED1") (pin "A") (pinfunction "A_A") (pintype "passive"))
      (node (ref "R20") (pin "1") (pinfunction "1_1") (pintype "passive"))
    )
    (net (code "36") (name "Net-(RGB1-BLUE_C)") (class "Default")
      (node (ref "PS1") (pin "4") (pinfunction "4_4") (pintype "passive"))
      (node (ref "RGB1") (pin "4") (pinfunction "BLUE_C_4") (pintype "bidirectional"))
    )
    (net (code "37") (name "Net-(RGB1-GREEN_C)") (class "Default")
      (node (ref "PS1") (pin "6") (pinfunction "6_6") (pintype "passive"))
      (node (ref "RGB1") (pin "6") (pinfunction "GREEN_C_6") (pintype "bidirectional"))
    )
    (net (code "38") (name "Net-(RGB1-RED_C)") (class "Default")
      (node (ref "PS1") (pin "3") (pinfunction "3_3") (pintype "passive"))
      (node (ref "RGB1") (pin "5") (pinfunction "RED_C_5") (pintype "bidirectional"))
    )
    (net (code "39") (name "Net-(RGB2-BLUE_C)") (class "Default")
      (node (ref "PS2") (pin "4") (pinfunction "4_4") (pintype "passive"))
      (node (ref "RGB2") (pin "4") (pinfunction "BLUE_C_4") (pintype "bidirectional"))
    )
    (net (code "40") (name "Net-(RGB2-GREEN_C)") (class "Default")
      (node (ref "PS2") (pin "6") (pinfunction "6_6") (pintype "passive"))
      (node (ref "RGB2") (pin "6") (pinfunction "GREEN_C_6") (pintype "bidirectional"))
    )
    (net (code "41") (name "Net-(RGB2-RED_C)") (class "Default")
      (node (ref "PS2") (pin "3") (pinfunction "3_3") (pintype "passive"))
      (node (ref "RGB2") (pin "5") (pinfunction "RED_C_5") (pintype "bidirectional"))
    )
    (net (code "42") (name "Net-(RGB3-BLUE_C)") (class "Default")
      (node (ref "PS3") (pin "4") (pinfunction "4_4") (pintype "passive"))
      (node (ref "RGB3") (pin "4") (pinfunction "BLUE_C_4") (pintype "bidirectional"))
    )
    (net (code "43") (name "Net-(RGB3-GREEN_C)") (class "Default")
      (node (ref "PS3") (pin "6") (pinfunction "6_6") (pintype "passive"))
      (node (ref "RGB3") (pin "6") (pinfunction "GREEN_C_6") (pintype "bidirectional"))
    )
    (net (code "44") (name "Net-(RGB3-RED_C)") (class "Default")
      (node (ref "PS3") (pin "3") (pinfunction "3_3") (pintype "passive"))
      (node (ref "RGB3") (pin "5") (pinfunction "RED_C_5") (pintype "bidirectional"))
    )
    (net (code "45") (name "Net-(RGB4-BLUE_C)") (class "Default")
      (node (ref "PS4") (pin "4") (pinfunction "4_4") (pintype "passive"))
      (node (ref "RGB4") (pin "4") (pinfunction "BLUE_C_4") (pintype "bidirectional"))
    )
    (net (code "46") (name "Net-(RGB4-GREEN_C)") (class "Default")
      (node (ref "PS4") (pin "6") (pinfunction "6_6") (pintype "passive"))
      (node (ref "RGB4") (pin "6") (pinfunction "GREEN_C_6") (pintype "bidirectional"))
    )
    (net (code "47") (name "Net-(RGB4-RED_C)") (class "Default")
      (node (ref "PS4") (pin "3") (pinfunction "3_3") (pintype "passive"))
      (node (ref "RGB4") (pin "5") (pinfunction "RED_C_5") (pintype "bidirectional"))
    )
    (net (code "48") (name "Net-(RGB5-BLUE_C)") (class "Default")
      (node (ref "PS5") (pin "4") (pinfunction "4_4") (pintype "passive"))
      (node (ref "RGB5") (pin "4") (pinfunction "BLUE_C_4") (pintype "bidirectional"))
    )
    (net (code "49") (name "Net-(RGB5-GREEN_C)") (class "Default")
      (node (ref "PS5") (pin "6") (pinfunction "6_6") (pintype "passive"))
      (node (ref "RGB5") (pin "6") (pinfunction "GREEN_C_6") (pintype "bidirectional"))
    )
    (net (code "50") (name "Net-(RGB5-RED_C)") (class "Default")
      (node (ref "PS5") (pin "3") (pinfunction "3_3") (pintype "passive"))
      (node (ref "RGB5") (pin "5") (pinfunction "RED_C_5") (pintype "bidirectional"))
    )
    (net (code "51") (name "Net-(RGB6-BLUE_C)") (class "Default")
      (node (ref "PS6") (pin "4") (pinfunction "4_4") (pintype "passive"))
      (node (ref "RGB6") (pin "4") (pinfunction "BLUE_C_4") (pintype "bidirectional"))
    )
    (net (code "52") (name "Net-(RGB6-GREEN_C)") (class "Default")
      (node (ref "PS6") (pin "6") (pinfunction "6_6") (pintype "passive"))
      (node (ref "RGB6") (pin "6") (pinfunction "GREEN_C_6") (pintype "bidirectional"))
    )
    (net (code "53") (name "Net-(RGB6-RED_C)") (class "Default")
      (node (ref "PS6") (pin "3") (pinfunction "3_3") (pintype "passive"))
      (node (ref "RGB6") (pin "5") (pinfunction "RED_C_5") (pintype "bidirectional"))
    )
    (net (code "54") (name "Net-(RGB7-BLUE_C)") (class "Default")
      (node (ref "PS7") (pin "4") (pinfunction "4_4") (pintype "passive"))
      (node (ref "RGB7") (pin "4") (pinfunction "BLUE_C_4") (pintype "bidirectional"))
    )
    (net (code "55") (name "Net-(RGB7-GREEN_C)") (class "Default")
      (node (ref "PS7") (pin "6") (pinfunction "6_6") (pintype "passive"))
      (node (ref "RGB7") (pin "6") (pinfunction "GREEN_C_6") (pintype "bidirectional"))
    )
    (net (code "56") (name "Net-(RGB7-RED_C)") (class "Default")
      (node (ref "PS7") (pin "3") (pinfunction "3_3") (pintype "passive"))
      (node (ref "RGB7") (pin "5") (pinfunction "RED_C_5") (pintype "bidirectional"))
    )
    (net (code "57") (name "Net-(RGB8-BLUE_C)") (class "Default")
      (node (ref "PS8") (pin "4") (pinfunction "4_4") (pintype "passive"))
      (node (ref "RGB8") (pin "4") (pinfunction "BLUE_C_4") (pintype "bidirectional"))
    )
    (net (code "58") (name "Net-(RGB8-GREEN_C)") (class "Default")
      (node (ref "PS8") (pin "6") (pinfunction "6_6") (pintype "passive"))
      (node (ref "RGB8") (pin "6") (pinfunction "GREEN_C_6") (pintype "bidirectional"))
    )
    (net (code "59") (name "Net-(RGB8-RED_C)") (class "Default")
      (node (ref "PS8") (pin "3") (pinfunction "3_3") (pintype "passive"))
      (node (ref "RGB8") (pin "5") (pinfunction "RED_C_5") (pintype "bidirectional"))
    )
    (net (code "60") (name "Net-(RGB9-BLUE_C)") (class "Default")
      (node (ref "PS9") (pin "4") (pinfunction "4_4") (pintype "passive"))
      (node (ref "RGB9") (pin "4") (pinfunction "BLUE_C_4") (pintype "bidirectional"))
    )
    (net (code "61") (name "Net-(RGB9-GREEN_C)") (class "Default")
      (node (ref "PS9") (pin "6") (pinfunction "6_6") (pintype "passive"))
      (node (ref "RGB9") (pin "6") (pinfunction "GREEN_C_6") (pintype "bidirectional"))
    )
    (net (code "62") (name "Net-(RGB9-RED_C)") (class "Default")
      (node (ref "PS9") (pin "3") (pinfunction "3_3") (pintype "passive"))
      (node (ref "RGB9") (pin "5") (pinfunction "RED_C_5") (pintype "bidirectional"))
    )
    (net (code "63") (name "Net-(RGB10-BLUE_C)") (class "Default")
      (node (ref "PS10") (pin "4") (pinfunction "4_4") (pintype "passive"))
      (node (ref "RGB10") (pin "4") (pinfunction "BLUE_C_4") (pintype "bidirectional"))
    )
    (net (code "64") (name "Net-(RGB10-GREEN_C)") (class "Default")
      (node (ref "PS10") (pin "6") (pinfunction "6_6") (pintype "passive"))
      (node (ref "RGB10") (pin "6") (pinfunction "GREEN_C_6") (pintype "bidirectional"))
    )
    (net (code "65") (name "Net-(RGB10-RED_C)") (class "Default")
      (node (ref "PS10") (pin "3") (pinfunction "3_3") (pintype "passive"))
      (node (ref "RGB10") (pin "5") (pinfunction "RED_C_5") (pintype "bidirectional"))
    )
    (net (code "66") (name "Net-(S1-P)") (class "Default")
      (node (ref "PS2") (pin "5") (pinfunction "5_5") (pintype "passive"))
      (node (ref "S1") (pin "3") (pinfunction "P_3") (pintype "passive"))
      (node (ref "S1") (pin "4") (pinfunction "P1_4") (pintype "passive"))
    )
    (net (code "67") (name "Net-(S2-P)") (class "Default")
      (node (ref "PS3") (pin "5") (pinfunction "5_5") (pintype "passive"))
      (node (ref "S2") (pin "3") (pinfunction "P_3") (pintype "passive"))
      (node (ref "S2") (pin "4") (pinfunction "P1_4") (pintype "passive"))
    )
    (net (code "68") (name "Net-(S3-P)") (class "Default")
      (node (ref "PS4") (pin "5") (pinfunction "5_5") (pintype "passive"))
      (node (ref "S3") (pin "3") (pinfunction "P_3") (pintype "passive"))
      (node (ref "S3") (pin "4") (pinfunction "P1_4") (pintype "passive"))
    )
    (net (code "69") (name "Net-(S4-P)") (class "Default")
      (node (ref "PS5") (pin "5") (pinfunction "5_5") (pintype "passive"))
      (node (ref "S4") (pin "3") (pinfunction "P_3") (pintype "passive"))
      (node (ref "S4") (pin "4") (pinfunction "P1_4") (pintype "passive"))
    )
    (net (code "70") (name "Net-(S5-P)") (class "Default")
      (node (ref "PS6") (pin "5") (pinfunction "5_5") (pintype "passive"))
      (node (ref "S5") (pin "3") (pinfunction "P_3") (pintype "passive"))
      (node (ref "S5") (pin "4") (pinfunction "P1_4") (pintype "passive"))
    )
    (net (code "71") (name "Net-(S6-P)") (class "Default")
      (node (ref "PS7") (pin "5") (pinfunction "5_5") (pintype "passive"))
      (node (ref "S6") (pin "3") (pinfunction "P_3") (pintype "passive"))
      (node (ref "S6") (pin "4") (pinfunction "P1_4") (pintype "passive"))
    )
    (net (code "72") (name "Net-(S7-P)") (class "Default")
      (node (ref "PS1") (pin "5") (pinfunction "5_5") (pintype "passive"))
      (node (ref "S7") (pin "3") (pinfunction "P_3") (pintype "passive"))
      (node (ref "S7") (pin "4") (pinfunction "P1_4") (pintype "passive"))
    )
    (net (code "73") (name "Net-(S8-P)") (class "Default")
      (node (ref "PS8") (pin "5") (pinfunction "5_5") (pintype "passive"))
      (node (ref "S8") (pin "3") (pinfunction "P_3") (pintype "passive"))
      (node (ref "S8") (pin "4") (pinfunction "P1_4") (pintype "passive"))
    )
    (net (code "74") (name "Net-(S9-P)") (class "Default")
      (node (ref "PS9") (pin "5") (pinfunction "5_5") (pintype "passive"))
      (node (ref "S9") (pin "3") (pinfunction "P_3") (pintype "passive"))
      (node (ref "S9") (pin "4") (pinfunction "P1_4") (pintype "passive"))
    )
    (net (code "75") (name "Net-(S10-P)") (class "Default")
      (node (ref "PS10") (pin "5") (pinfunction "5_5") (pintype "passive"))
      (node (ref "S10") (pin "3") (pinfunction "P_3") (pintype "passive"))
      (node (ref "S10") (pin "4") (pinfunction "P1_4") (pintype "passive"))
    )
    (net (code "76") (name "Net-(U1-DO)") (class "Default")
      (node (ref "U1") (pin "5") (pinfunction "DO_5") (pintype "output"))
      (node (ref "U2") (pin "6") (pinfunction "DIN_6") (pintype "input"))
    )
    (net (code "77") (name "Net-(U1-OUTB)") (class "Default")
      (node (ref "SV1") (pin "4") (pinfunction "4_4") (pintype "passive"))
      (node (ref "U1") (pin "3") (pinfunction "OUTB_3") (pintype "open_collector"))
    )
    (net (code "78") (name "Net-(U1-OUTG)") (class "Default")
      (node (ref "SV1") (pin "6") (pinfunction "6_6") (pintype "passive"))
      (node (ref "U1") (pin "1") (pinfunction "OUTG_1") (pintype "open_collector"))
    )
    (net (code "79") (name "Net-(U1-OUTR)") (class "Default")
      (node (ref "SV1") (pin "3") (pinfunction "3_3") (pintype "passive"))
      (node (ref "U1") (pin "2") (pinfunction "OUTR_2") (pintype "open_collector"))
    )
    (net (code "80") (name "Net-(U1-VDD)") (class "Default")
      (node (ref "C1") (pin "1") (pinfunction "1_1") (pintype "passive"))
      (node (ref "R1") (pin "1") (pinfunction "1_1") (pintype "passive"))
      (node (ref "U1") (pin "8") (pinfunction "VDD_8") (pintype "power_in"))
    )
    (net (code "81") (name "Net-(U2-DO)") (class "Default")
      (node (ref "U2") (pin "5") (pinfunction "DO_5") (pintype "output"))
      (node (ref "U3") (pin "6") (pinfunction "DIN_6") (pintype "input"))
    )
    (net (code "82") (name "Net-(U2-OUTB)") (class "Default")
      (node (ref "SV2") (pin "4") (pinfunction "4_4") (pintype "passive"))
      (node (ref "U2") (pin "3") (pinfunction "OUTB_3") (pintype "open_collector"))
    )
    (net (code "83") (name "Net-(U2-OUTG)") (class "Default")
      (node (ref "SV2") (pin "6") (pinfunction "6_6") (pintype "passive"))
      (node (ref "U2") (pin "1") (pinfunction "OUTG_1") (pintype "open_collector"))
    )
    (net (code "84") (name "Net-(U2-OUTR)") (class "Default")
      (node (ref "SV2") (pin "3") (pinfunction "3_3") (pintype "passive"))
      (node (ref "U2") (pin "2") (pinfunction "OUTR_2") (pintype "open_collector"))
    )
    (net (code "85") (name "Net-(U2-VDD)") (class "Default")
      (node (ref "C2") (pin "1") (pinfunction "1_1") (pintype "passive"))
      (node (ref "R2") (pin "1") (pinfunction "1_1") (pintype "passive"))
      (node (ref "U2") (pin "8") (pinfunction "VDD_8") (pintype "power_in"))
    )
    (net (code "86") (name "Net-(U3-DO)") (class "Default")
      (node (ref "U3") (pin "5") (pinfunction "DO_5") (pintype "output"))
      (node (ref "U4") (pin "6") (pinfunction "DIN_6") (pintype "input"))
    )
    (net (code "87") (name "Net-(U3-OUTB)") (class "Default")
      (node (ref "SV3") (pin "4") (pinfunction "4_4") (pintype "passive"))
      (node (ref "U3") (pin "3") (pinfunction "OUTB_3") (pintype "open_collector"))
    )
    (net (code "88") (name "Net-(U3-OUTG)") (class "Default")
      (node (ref "SV3") (pin "6") (pinfunction "6_6") (pintype "passive"))
      (node (ref "U3") (pin "1") (pinfunction "OUTG_1") (pintype "open_collector"))
    )
    (net (code "89") (name "Net-(U3-OUTR)") (class "Default")
      (node (ref "SV3") (pin "3") (pinfunction "3_3") (pintype "passive"))
      (node (ref "U3") (pin "2") (pinfunction "OUTR_2") (pintype "open_collector"))
    )
    (net (code "90") (name "Net-(U3-VDD)") (class "Default")
      (node (ref "C3") (pin "1") (pinfunction "1_1") (pintype "passive"))
      (node (ref "R3") (pin "1") (pinfunction "1_1") (pintype "passive"))
      (node (ref "U3") (pin "8") (pinfunction "VDD_8") (pintype "power_in"))
    )
    (net (code "91") (name "Net-(U4-DO)") (class "Default")
      (node (ref "U4") (pin "5") (pinfunction "DO_5") (pintype "output"))
      (node (ref "U5") (pin "6") (pinfunction "DIN_6") (pintype "input"))
    )
    (net (code "92") (name "Net-(U4-OUTB)") (class "Default")
      (node (ref "SV4") (pin "4") (pinfunction "4_4") (pintype "passive"))
      (node (ref "U4") (pin "3") (pinfunction "OUTB_3") (pintype "open_collector"))
    )
    (net (code "93") (name "Net-(U4-OUTG)") (class "Default")
      (node (ref "SV4") (pin "6") (pinfunction "6_6") (pintype "passive"))
      (node (ref "U4") (pin "1") (pinfunction "OUTG_1") (pintype "open_collector"))
    )
    (net (code "94") (name "Net-(U4-OUTR)") (class "Default")
      (node (ref "SV4") (pin "3") (pinfunction "3_3") (pintype "passive"))
      (node (ref "U4") (pin "2") (pinfunction "OUTR_2") (pintype "open_collector"))
    )
    (net (code "95") (name "Net-(U4-VDD)") (class "Default")
      (node (ref "C4") (pin "1") (pinfunction "1_1") (pintype "passive"))
      (node (ref "R4") (pin "1") (pinfunction "1_1") (pintype "passive"))
      (node (ref "U4") (pin "8") (pinfunction "VDD_8") (pintype "power_in"))
    )
    (net (code "96") (name "Net-(U5-DO)") (class "Default")
      (node (ref "U5") (pin "5") (pinfunction "DO_5") (pintype "output"))
      (node (ref "U6") (pin "6") (pinfunction "DIN_6") (pintype "input"))
    )
    (net (code "97") (name "Net-(U5-OUTB)") (class "Default")
      (node (ref "SV5") (pin "4") (pinfunction "4_4") (pintype "passive"))
      (node (ref "U5") (pin "3") (pinfunction "OUTB_3") (pintype "open_collector"))
    )
    (net (code "98") (name "Net-(U5-OUTG)") (class "Default")
      (node (ref "SV5") (pin "6") (pinfunction "6_6") (pintype "passive"))
      (node (ref "U5") (pin "1") (pinfunction "OUTG_1") (pintype "open_collector"))
    )
    (net (code "99") (name "Net-(U5-OUTR)") (class "Default")
      (node (ref "SV5") (pin "3") (pinfunction "3_3") (pintype "passive"))
      (node (ref "U5") (pin "2") (pinfunction "OUTR_2") (pintype "open_collector"))
    )
    (net (code "100") (name "Net-(U5-VDD)") (class "Default")
      (node (ref "C5") (pin "1") (pinfunction "1_1") (pintype "passive"))
      (node (ref "R5") (pin "1") (pinfunction "1_1") (pintype "passive"))
      (node (ref "U5") (pin "8") (pinfunction "VDD_8") (pintype "power_in"))
    )
    (net (code "101") (name "Net-(U6-DO)") (class "Default")
      (node (ref "U6") (pin "5") (pinfunction "DO_5") (pintype "output"))
      (node (ref "U7") (pin "6") (pinfunction "DIN_6") (pintype "input"))
    )
    (net (code "102") (name "Net-(U6-VDD)") (class "Default")
      (node (ref "C6") (pin "1") (pinfunction "1_1") (pintype "passive"))
      (node (ref "R6") (pin "1") (pinfunction "1_1") (pintype "passive"))
      (node (ref "U6") (pin "8") (pinfunction "VDD_8") (pintype "power_in"))
    )
    (net (code "103") (name "Net-(U7-DO)") (class "Default")
      (node (ref "U7") (pin "5") (pinfunction "DO_5") (pintype "output"))
      (node (ref "U8") (pin "6") (pinfunction "DIN_6") (pintype "input"))
    )
    (net (code "104") (name "Net-(U7-OUTB)") (class "Default")
      (node (ref "SV7") (pin "4") (pinfunction "4_4") (pintype "passive"))
      (node (ref "U7") (pin "3") (pinfunction "OUTB_3") (pintype "open_collector"))
    )
    (net (code "105") (name "Net-(U7-OUTG)") (class "Default")
      (node (ref "SV7") (pin "6") (pinfunction "6_6") (pintype "passive"))
      (node (ref "U7") (pin "1") (pinfunction "OUTG_1") (pintype "open_collector"))
    )
    (net (code "106") (name "Net-(U7-OUTR)") (class "Default")
      (node (ref "SV7") (pin "3") (pinfunction "3_3") (pintype "passive"))
      (node (ref "U7") (pin "2") (pinfunction "OUTR_2") (pintype "open_collector"))
    )
    (net (code "107") (name "Net-(U7-VDD)") (class "Default")
      (node (ref "C7") (pin "1") (pinfunction "1_1") (pintype "passive"))
      (node (ref "R7") (pin "1") (pinfunction "1_1") (pintype "passive"))
      (node (ref "U7") (pin "8") (pinfunction "VDD_8") (pintype "power_in"))
    )
    (net (code "108") (name "Net-(U8-DO)") (class "Default")
      (node (ref "U8") (pin "5") (pinfunction "DO_5") (pintype "output"))
      (node (ref "U9") (pin "6") (pinfunction "DIN_6") (pintype "input"))
    )
    (net (code "109") (name "Net-(U8-VDD)") (class "Default")
      (node (ref "C8") (pin "1") (pinfunction "1_1") (pintype "passive"))
      (node (ref "R8") (pin "1") (pinfunction "1_1") (pintype "passive"))
      (node (ref "U8") (pin "8") (pinfunction "VDD_8") (pintype "power_in"))
    )
    (net (code "110") (name "Net-(U9-OUTB)") (class "Default")
      (node (ref "SV9") (pin "4") (pinfunction "4_4") (pintype "passive"))
      (node (ref "U9") (pin "3") (pinfunction "OUTB_3") (pintype "open_collector"))
    )
    (net (code "111") (name "Net-(U9-OUTG)") (class "Default")
      (node (ref "SV9") (pin "6") (pinfunction "6_6") (pintype "passive"))
      (node (ref "U9") (pin "1") (pinfunction "OUTG_1") (pintype "open_collector"))
    )
    (net (code "112") (name "Net-(U9-OUTR)") (class "Default")
      (node (ref "SV9") (pin "3") (pinfunction "3_3") (pintype "passive"))
      (node (ref "U9") (pin "2") (pinfunction "OUTR_2") (pintype "open_collector"))
    )
    (net (code "113") (name "Net-(U9-VDD)") (class "Default")
      (node (ref "C9") (pin "1") (pinfunction "1_1") (pintype "passive"))
      (node (ref "R9") (pin "1") (pinfunction "1_1") (pintype "passive"))
      (node (ref "U9") (pin "8") (pinfunction "VDD_8") (pintype "power_in"))
    )
    (net (code "114") (name "Net-(U10-DIN)") (class "Default")
      (node (ref "U10") (pin "6") (pinfunction "DIN_6") (pintype "input"))
      (node (ref "U9") (pin "5") (pinfunction "DO_5") (pintype "output"))
    )
    (net (code "115") (name "Net-(U10-OUTB)") (class "Default")
      (node (ref "SV10") (pin "4") (pinfunction "4_4") (pintype "passive"))
      (node (ref "U10") (pin "3") (pinfunction "OUTB_3") (pintype "open_collector"))
    )
    (net (code "116") (name "Net-(U10-OUTG)") (class "Default")
      (node (ref "SV10") (pin "6") (pinfunction "6_6") (pintype "passive"))
      (node (ref "U10") (pin "1") (pinfunction "OUTG_1") (pintype "open_collector"))
    )
    (net (code "117") (name "Net-(U10-OUTR)") (class "Default")
      (node (ref "SV10") (pin "3") (pinfunction "3_3") (pintype "passive"))
      (node (ref "U10") (pin "2") (pinfunction "OUTR_2") (pintype "open_collector"))
    )
    (net (code "118") (name "Net-(U10-VDD)") (class "Default")
      (node (ref "C10") (pin "1") (pinfunction "1_1") (pintype "passive"))
      (node (ref "R10") (pin "1") (pinfunction "1_1") (pintype "passive"))
      (node (ref "U10") (pin "8") (pinfunction "VDD_8") (pintype "power_in"))
    )
    (net (code "119") (name "R6") (class "Default")
      (node (ref "SV6") (pin "3") (pinfunction "3_3") (pintype "passive"))
      (node (ref "U6") (pin "2") (pinfunction "OUTR_2") (pintype "open_collector"))
    )
    (net (code "120") (name "R8") (class "Default")
      (node (ref "SV8") (pin "3") (pinfunction "3_3") (pintype "passive"))
      (node (ref "U8") (pin "2") (pinfunction "OUTR_2") (pintype "open_collector"))
    )
    (net (code "121") (name "RESERVE") (class "Default")
      (node (ref "END1") (pin "2") (pinfunction "2_2") (pintype "passive"))
      (node (ref "END1_PIN") (pin "1") (pinfunction "1_1") (pintype "passive"))
      (node (ref "INP") (pin "8") (pinfunction "8_8") (pintype "passive"))
      (node (ref "OUTP") (pin "8") (pinfunction "8_8") (pintype "passive"))
    )
    (net (code "122") (name "RESET") (class "Default")
      (node (ref "IC1") (pin "15") (pinfunction "RES_15") (pintype "input"))
      (node (ref "IC2") (pin "8") (pinfunction "I0_8") (pintype "input"))
      (node (ref "IC2") (pin "9") (pinfunction "I1_9") (pintype "input"))
      (node (ref "INP") (pin "6") (pinfunction "6_6") (pintype "passive"))
    )
    (net (code "123") (name "RESET_OUT") (class "Default")
      (node (ref "IC2") (pin "11") (pinfunction "O_11") (pintype "output"))
      (node (ref "OUTP") (pin "6") (pinfunction "6_6") (pintype "passive"))
    )
    (net (code "124") (name "RETURN") (class "Default")
      (node (ref "END") (pin "1") (pinfunction "1_1") (pintype "passive"))
      (node (ref "END_PIN") (pin "2") (pinfunction "2_2") (pintype "passive"))
      (node (ref "INP") (pin "2") (pinfunction "2_2") (pintype "passive"))
      (node (ref "OUTP") (pin "2") (pinfunction "2_2") (pintype "passive"))
    )
    (net (code "125") (name "unconnected-(IC1A-CO-Pad12)") (class "Default")
      (node (ref "IC1") (pin "12") (pinfunction "CO_12") (pintype "output"))
    )
    (net (code "126") (name "unconnected-(U1-SET-Pad7)") (class "Default")
      (node (ref "U1") (pin "7") (pinfunction "SET_7") (pintype "bidirectional"))
    )
    (net (code "127") (name "unconnected-(U2-SET-Pad7)") (class "Default")
      (node (ref "U2") (pin "7") (pinfunction "SET_7") (pintype "bidirectional"))
    )
    (net (code "128") (name "unconnected-(U3-SET-Pad7)") (class "Default")
      (node (ref "U3") (pin "7") (pinfunction "SET_7") (pintype "bidirectional"))
    )
    (net (code "129") (name "unconnected-(U4-SET-Pad7)") (class "Default")
      (node (ref "U4") (pin "7") (pinfunction "SET_7") (pintype "bidirectional"))
    )
    (net (code "130") (name "unconnected-(U5-SET-Pad7)") (class "Default")
      (node (ref "U5") (pin "7") (pinfunction "SET_7") (pintype "bidirectional"))
    )
    (net (code "131") (name "unconnected-(U6-SET-Pad7)") (class "Default")
      (node (ref "U6") (pin "7") (pinfunction "SET_7") (pintype "bidirectional"))
    )
    (net (code "132") (name "unconnected-(U7-SET-Pad7)") (class "Default")
      (node (ref "U7") (pin "7") (pinfunction "SET_7") (pintype "bidirectional"))
    )
    (net (code "133") (name "unconnected-(U8-SET-Pad7)") (class "Default")
      (node (ref "U8") (pin "7") (pinfunction "SET_7") (pintype "bidirectional"))
    )
    (net (code "134") (name "unconnected-(U9-SET-Pad7)") (class "Default")
      (node (ref "U9") (pin "7") (pinfunction "SET_7") (pintype "bidirectional"))
    )
    (net (code "135") (name "unconnected-(U10-SET-Pad7)") (class "Default")
      (node (ref "U10") (pin "7") (pinfunction "SET_7") (pintype "bidirectional"))
    )
  )
)
